# rgb-led-cc-driver-mk-2_0.net
KiCad netlist of a schematic drawn in EAGLE
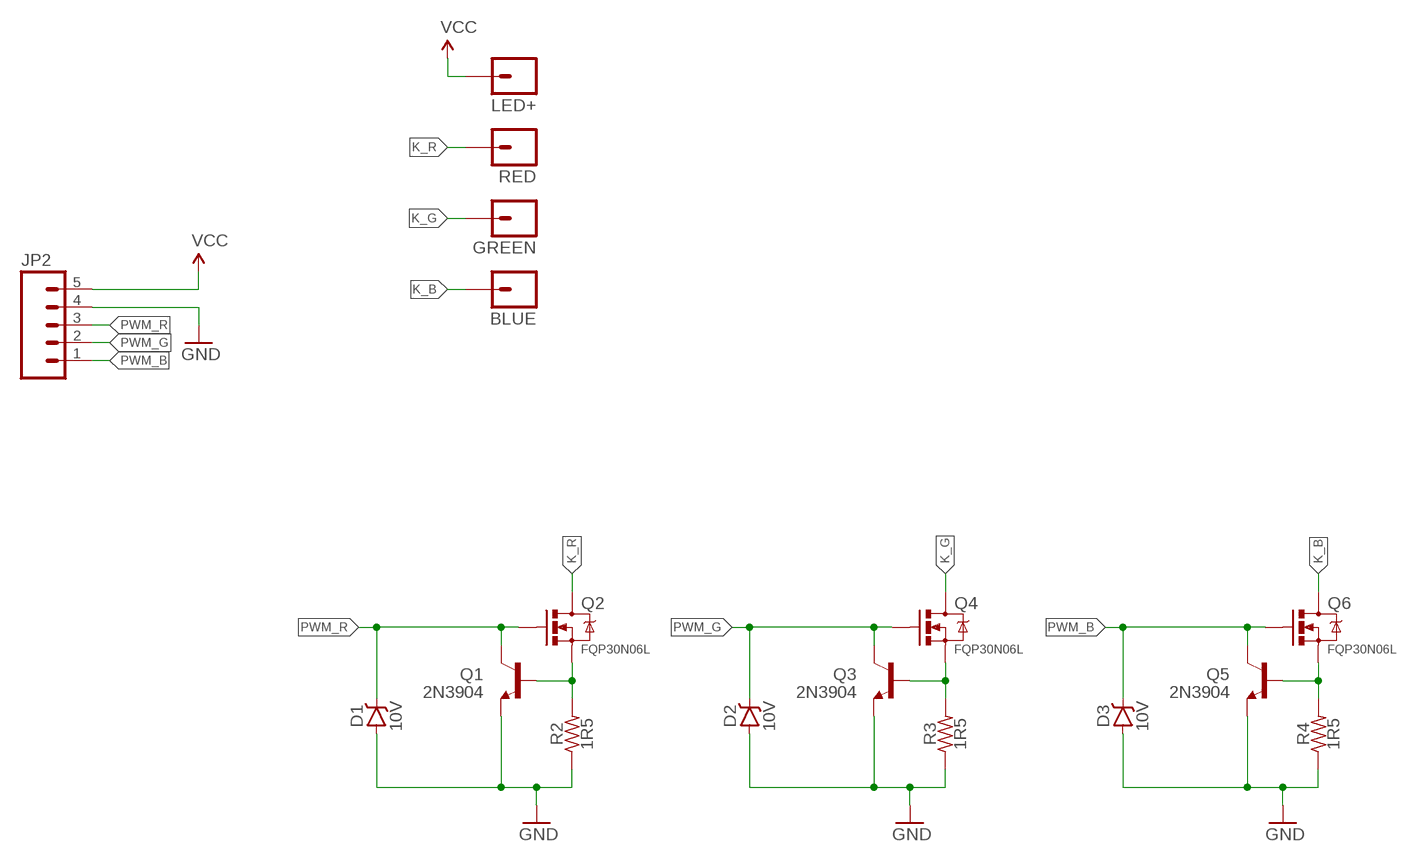
[diagram p0: schematic, sheet 1]

(export (version "E")
  (design (tool "Eeschema 10.0.6"))
  (components
    (comp (ref "BLUE")
      (value "M01PTH_2MM")
      (footprint "eagle-import:1X01_2MM")
      (libsource (lib "eagle-import") (part "M01PTH_2MM"))
    )
    (comp (ref "D1")
      (value "10V")
      (footprint "eagle-import:DIODE-ZENNER-7.62MM")
      (libsource (lib "eagle-import") (part "DIODE-ZENER7.62MM-PTH"))
    )
    (comp (ref "D2")
      (value "10V")
      (footprint "eagle-import:DIODE-ZENNER-7.62MM")
      (libsource (lib "eagle-import") (part "DIODE-ZENER7.62MM-PTH"))
    )
    (comp (ref "D3")
      (value "10V")
      (footprint "eagle-import:DIODE-ZENNER-7.62MM")
      (libsource (lib "eagle-import") (part "DIODE-ZENER7.62MM-PTH"))
    )
    (comp (ref "GREEN")
      (value "M01PTH_2MM")
      (footprint "eagle-import:1X01_2MM")
      (libsource (lib "eagle-import") (part "M01PTH_2MM"))
    )
    (comp (ref "JP2")
      (value "M05PTH")
      (footprint "eagle-import:1X05")
      (libsource (lib "eagle-import") (part "M05PTH"))
    )
    (comp (ref "LED+")
      (value "M01PTH_2MM")
      (footprint "eagle-import:1X01_2MM")
      (libsource (lib "eagle-import") (part "M01PTH_2MM"))
    )
    (comp (ref "Q1")
      (value "2N3904")
      (footprint "eagle-import:TO-92-AMMO")
      (libsource (lib "eagle-import") (part "TRANSISTOR_NPNTO-92-AMMO-EBC"))
    )
    (comp (ref "Q2")
      (value "FQP30N06L")
      (footprint "eagle-import:TO220-THERMPAD")
      (libsource (lib "eagle-import") (part "MOSFET-NCHANNELTO-220"))
    )
    (comp (ref "Q3")
      (value "2N3904")
      (footprint "eagle-import:TO-92-AMMO")
      (libsource (lib "eagle-import") (part "TRANSISTOR_NPNTO-92-AMMO-EBC"))
    )
    (comp (ref "Q4")
      (value "FQP30N06L")
      (footprint "eagle-import:TO220-THERMPAD")
      (libsource (lib "eagle-import") (part "MOSFET-NCHANNELTO-220"))
    )
    (comp (ref "Q5")
      (value "2N3904")
      (footprint "eagle-import:TO-92-AMMO")
      (libsource (lib "eagle-import") (part "TRANSISTOR_NPNTO-92-AMMO-EBC"))
    )
    (comp (ref "Q6")
      (value "FQP30N06L")
      (footprint "eagle-import:TO220-THERMPAD")
      (libsource (lib "eagle-import") (part "MOSFET-NCHANNELTO-220"))
    )
    (comp (ref "R2")
      (value "1R5")
      (footprint "eagle-import:RESISTOR-AXIAL-PTH-10.16MM")
      (libsource (lib "eagle-import") (part "RESISTORPTH-AXIAL-10.16MM"))
    )
    (comp (ref "R3")
      (value "1R5")
      (footprint "eagle-import:RESISTOR-AXIAL-PTH-10.16MM")
      (libsource (lib "eagle-import") (part "RESISTORPTH-AXIAL-10.16MM"))
    )
    (comp (ref "R4")
      (value "1R5")
      (footprint "eagle-import:RESISTOR-AXIAL-PTH-10.16MM")
      (libsource (lib "eagle-import") (part "RESISTORPTH-AXIAL-10.16MM"))
    )
    (comp (ref "RED")
      (value "M01PTH_2MM")
      (footprint "eagle-import:1X01_2MM")
      (libsource (lib "eagle-import") (part "M01PTH_2MM"))
    )
  )
  (nets
    (net (code "1") (name "GND") (class "Default")
      (node (ref "D1") (pin "A") (pinfunction "A_A") (pintype "passive"))
      (node (ref "D2") (pin "A") (pinfunction "A_A") (pintype "passive"))
      (node (ref "D3") (pin "A") (pinfunction "A_A") (pintype "passive"))
      (node (ref "JP2") (pin "4") (pinfunction "4_4") (pintype "passive"))
      (node (ref "Q1") (pin "1") (pinfunction "E_1") (pintype "passive"))
      (node (ref "Q3") (pin "1") (pinfunction "E_1") (pintype "passive"))
      (node (ref "Q5") (pin "1") (pinfunction "E_1") (pintype "passive"))
      (node (ref "R2") (pin "P$1") (pinfunction "1_P$1") (pintype "passive"))
      (node (ref "R3") (pin "P$1") (pinfunction "1_P$1") (pintype "passive"))
      (node (ref "R4") (pin "P$1") (pinfunction "1_P$1") (pintype "passive"))
    )
    (net (code "2") (name "K_B") (class "Default")
      (node (ref "BLUE") (pin "1") (pinfunction "1_1") (pintype "passive"))
      (node (ref "Q6") (pin "2@1") (pinfunction "D_2@1") (pintype "passive"))
      (node (ref "Q6") (pin "2@2") (pinfunction "D_2@2") (pintype "passive"))
    )
    (net (code "3") (name "K_G") (class "Default")
      (node (ref "GREEN") (pin "1") (pinfunction "1_1") (pintype "passive"))
      (node (ref "Q4") (pin "2@1") (pinfunction "D_2@1") (pintype "passive"))
      (node (ref "Q4") (pin "2@2") (pinfunction "D_2@2") (pintype "passive"))
    )
    (net (code "4") (name "K_R") (class "Default")
      (node (ref "Q2") (pin "2@1") (pinfunction "D_2@1") (pintype "passive"))
      (node (ref "Q2") (pin "2@2") (pinfunction "D_2@2") (pintype "passive"))
      (node (ref "RED") (pin "1") (pinfunction "1_1") (pintype "passive"))
    )
    (net (code "5") (name "Net-(Q1-B)") (class "Default")
      (node (ref "Q1") (pin "2") (pinfunction "B_2") (pintype "passive"))
      (node (ref "Q2") (pin "3") (pinfunction "S_3") (pintype "passive"))
      (node (ref "R2") (pin "P$2") (pinfunction "2_P$2") (pintype "passive"))
    )
    (net (code "6") (name "Net-(Q3-B)") (class "Default")
      (node (ref "Q3") (pin "2") (pinfunction "B_2") (pintype "passive"))
      (node (ref "Q4") (pin "3") (pinfunction "S_3") (pintype "passive"))
      (node (ref "R3") (pin "P$2") (pinfunction "2_P$2") (pintype "passive"))
    )
    (net (code "7") (name "Net-(Q5-B)") (class "Default")
      (node (ref "Q5") (pin "2") (pinfunction "B_2") (pintype "passive"))
      (node (ref "Q6") (pin "3") (pinfunction "S_3") (pintype "passive"))
      (node (ref "R4") (pin "P$2") (pinfunction "2_P$2") (pintype "passive"))
    )
    (net (code "8") (name "PWM_B") (class "Default")
      (node (ref "D3") (pin "K") (pinfunction "C_K") (pintype "passive"))
      (node (ref "JP2") (pin "1") (pinfunction "1_1") (pintype "passive"))
      (node (ref "Q5") (pin "3") (pinfunction "C_3") (pintype "passive"))
      (node (ref "Q6") (pin "1") (pinfunction "G_1") (pintype "passive"))
    )
    (net (code "9") (name "PWM_G") (class "Default")
      (node (ref "D2") (pin "K") (pinfunction "C_K") (pintype "passive"))
      (node (ref "JP2") (pin "2") (pinfunction "2_2") (pintype "passive"))
      (node (ref "Q3") (pin "3") (pinfunction "C_3") (pintype "passive"))
      (node (ref "Q4") (pin "1") (pinfunction "G_1") (pintype "passive"))
    )
    (net (code "10") (name "PWM_R") (class "Default")
      (node (ref "D1") (pin "K") (pinfunction "C_K") (pintype "passive"))
      (node (ref "JP2") (pin "3") (pinfunction "3_3") (pintype "passive"))
      (node (ref "Q1") (pin "3") (pinfunction "C_3") (pintype "passive"))
      (node (ref "Q2") (pin "1") (pinfunction "G_1") (pintype "passive"))
    )
    (net (code "11") (name "VCC") (class "Default")
      (node (ref "JP2") (pin "5") (pinfunction "5_5") (pintype "passive"))
      (node (ref "LED+") (pin "1") (pinfunction "1_1") (pintype "passive"))
    )
  )
)
